# TPDS300A_USB_Type-C_Port_Protection.net
KiCad netlist of a schematic drawn in Altium Designer
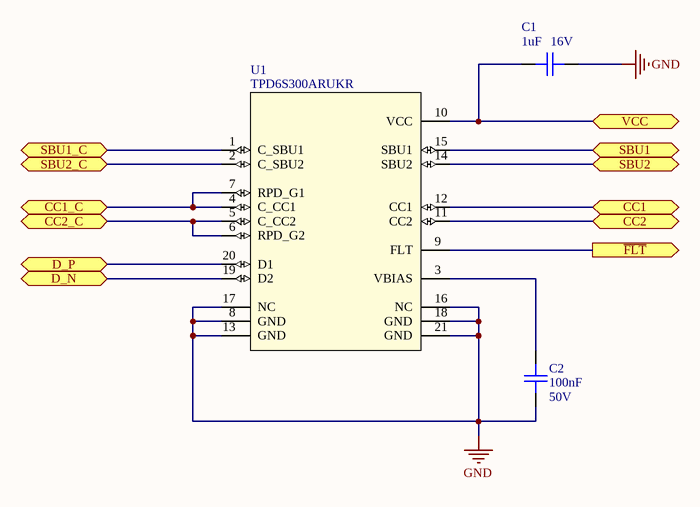
[diagram p0: TPDS300A_USB_Type-C_Port_Protection.SchDoc]

(export (version "E")
  (design (tool "Eeschema 10.0.6"))
  (components
    (comp (ref "C1")
      (value "CAP CER 1UF 16V X5R 0402")
      (footprint "C0402")
      (description "1µF ±10% 16V Ceramic Capacitor X5R 0402 (1005 Metric)")
      (fields
        (field (name "MANUFACTURER") "Yageo")
        (field (name "MANUFACTURER PART NUMBER") "CC0402KRX5R7BB105")
        (field (name "VOLTAGE RATING") "16V")
        (field (name "CAPACITANCE") "1uF")
      )
      (libsource (lib "capacitors_smd") (part "CAP CER 1UF 16V X5R 0402"))
    )
    (comp (ref "C2")
      (value "CAP CER 0.1UF 50V X7R 0402")
      (footprint "C0402")
      (description "0.1µF ±10% 50V Ceramic Capacitor X7R 0402 (1005 Metric)")
      (fields
        (field (name "MANUFACTURER") "TDK")
        (field (name "MANUFACTURER PART NUMBER") "CGA2B3X7R1H104K050BB")
        (field (name "CAPACITANCE") "100nF")
        (field (name "VOLTAGE") "50V")
      )
      (libsource (lib "capacitors_smd") (part "CAP CER 0.1UF 50V X7R 0402"))
    )
    (comp (ref "U1")
      (value "TPD6S300ARUKR")
      (footprint "WQFN20_RUK_TEX")
      (description "USB Type-C™ Port Protector: Short-to-VBUS Overvoltage  and IEC ESD Protection")
      (fields (field (name "MANUFACTURER") "Texas Instruments"))
      (libsource (lib "BLDC_Motor_Driver") (part "IC TPD6S300A USB-C ESD PROTECTION"))
    )
  )
  (nets
    (net (code "1") (name "/CC1") (class "Default")
      (node (ref "U1") (pin "12") (pinfunction "CC1_12") (pintype "bidirectional"))
    )
    (net (code "2") (name "/CC1_C") (class "Default")
      (node (ref "U1") (pin "4") (pinfunction "C_CC1_4") (pintype "bidirectional"))
      (node (ref "U1") (pin "7") (pinfunction "RPD_G1_7") (pintype "bidirectional"))
    )
    (net (code "3") (name "/CC2") (class "Default")
      (node (ref "U1") (pin "11") (pinfunction "CC2_11") (pintype "bidirectional"))
    )
    (net (code "4") (name "/CC2_C") (class "Default")
      (node (ref "U1") (pin "5") (pinfunction "C_CC2_5") (pintype "bidirectional"))
      (node (ref "U1") (pin "6") (pinfunction "RPD_G2_6") (pintype "bidirectional"))
    )
    (net (code "5") (name "/D_N") (class "Default")
      (node (ref "U1") (pin "19") (pinfunction "D2_19") (pintype "bidirectional"))
    )
    (net (code "6") (name "/D_P") (class "Default")
      (node (ref "U1") (pin "20") (pinfunction "D1_20") (pintype "bidirectional"))
    )
    (net (code "7") (name "/FLT") (class "Default")
      (node (ref "U1") (pin "9") (pinfunction "FLT_9") (pintype "open_collector"))
    )
    (net (code "8") (name "/SBU1") (class "Default")
      (node (ref "U1") (pin "15") (pinfunction "SBU1_15") (pintype "bidirectional"))
    )
    (net (code "9") (name "/SBU1_C") (class "Default")
      (node (ref "U1") (pin "1") (pinfunction "C_SBU1_1") (pintype "bidirectional"))
    )
    (net (code "10") (name "/SBU2") (class "Default")
      (node (ref "U1") (pin "14") (pinfunction "SBU2_14") (pintype "bidirectional"))
    )
    (net (code "11") (name "/SBU2_C") (class "Default")
      (node (ref "U1") (pin "2") (pinfunction "C_SBU2_2") (pintype "bidirectional"))
    )
    (net (code "12") (name "/VCC") (class "Default")
      (node (ref "C1") (pin "2") (pinfunction "2_2") (pintype "passive"))
      (node (ref "U1") (pin "10") (pinfunction "VCC_10") (pintype "power_in"))
    )
    (net (code "13") (name "GND") (class "Default")
      (node (ref "C1") (pin "1") (pinfunction "1_1") (pintype "passive"))
      (node (ref "C2") (pin "1") (pinfunction "1_1") (pintype "passive"))
      (node (ref "U1") (pin "13") (pinfunction "GND_13") (pintype "passive"))
      (node (ref "U1") (pin "16") (pinfunction "NC_16") (pintype "passive"))
      (node (ref "U1") (pin "17") (pinfunction "NC_17") (pintype "passive"))
      (node (ref "U1") (pin "18") (pinfunction "GND_18") (pintype "passive"))
      (node (ref "U1") (pin "21") (pinfunction "GND_21") (pintype "passive"))
      (node (ref "U1") (pin "8") (pinfunction "GND_8") (pintype "passive"))
    )
    (net (code "14") (name "Net-(U1-VBIAS)") (class "Default")
      (node (ref "C2") (pin "2") (pinfunction "2_2") (pintype "passive"))
      (node (ref "U1") (pin "3") (pinfunction "VBIAS_3") (pintype "power_in"))
    )
  )
)
